# Wii_U_GamePad.net
KiCad netlist of a schematic drawn in EAGLE
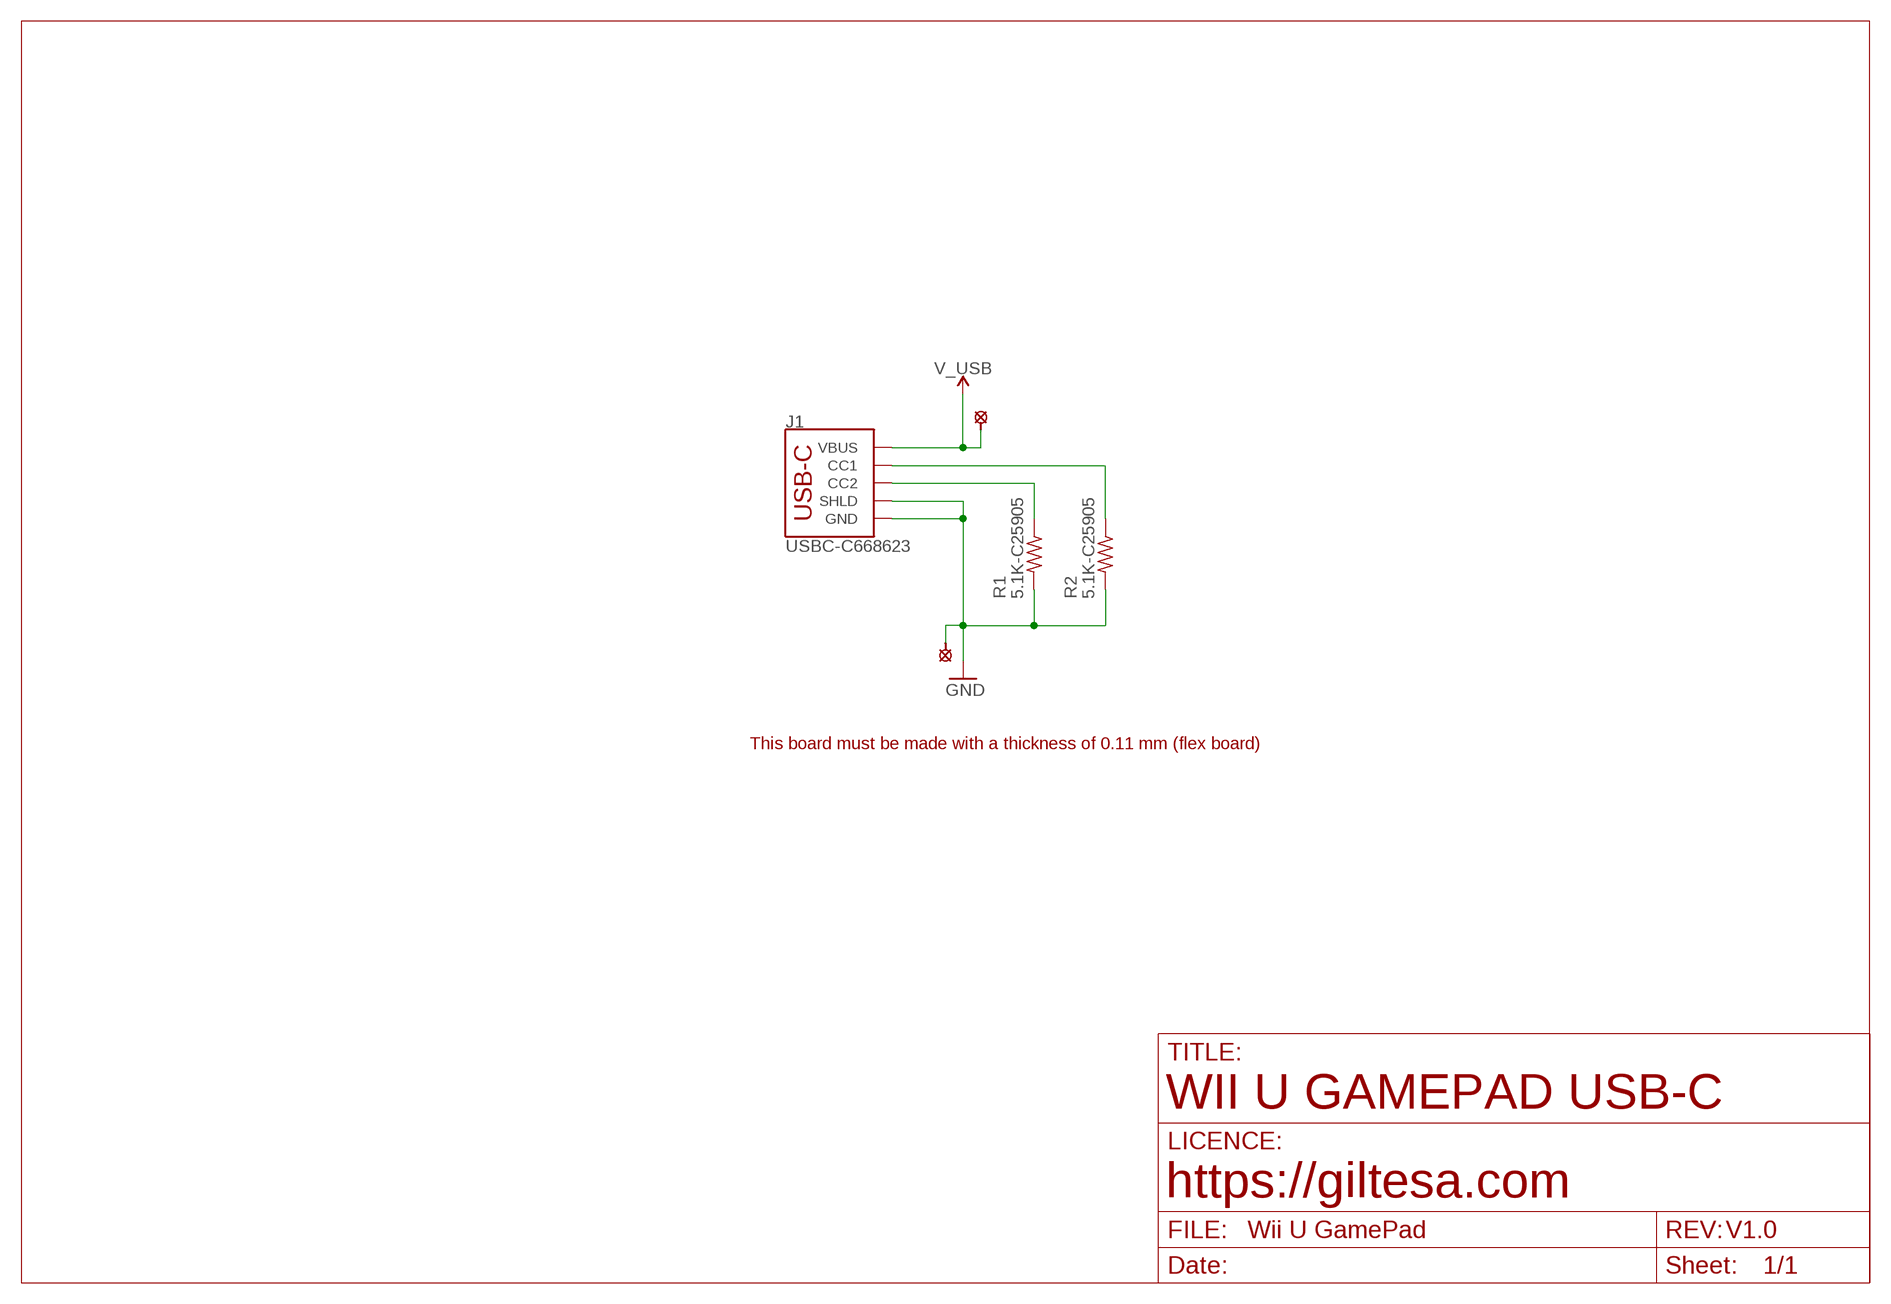
[diagram p0: schematic, sheet 1]

(export (version "E")
  (design (tool "Eeschema 10.0.6"))
  (components
    (comp (ref "J1")
      (value "USBC-C668623")
      (footprint "eagle-import:USB-C_6P_SMD_WIIU")
      (libsource (lib "eagle-import") (part "USB-C_6P_WIIU"))
    )
    (comp (ref "R1")
      (value "5.1K-C25905")
      (footprint "eagle-import:R0402")
      (libsource (lib "eagle-import") (part "R0402"))
    )
    (comp (ref "R2")
      (value "5.1K-C25905")
      (footprint "eagle-import:R0402")
      (libsource (lib "eagle-import") (part "R0402"))
    )
    (comp (ref "U$1")
      (value "PAD_1.7")
      (footprint "eagle-import:PAD_1.7")
      (libsource (lib "eagle-import") (part "PAD_1.7"))
    )
    (comp (ref "U$2")
      (value "PAD_1.7")
      (footprint "eagle-import:PAD_1.7")
      (libsource (lib "eagle-import") (part "PAD_1.7"))
    )
  )
  (nets
    (net (code "1") (name "GND") (class "Default")
      (node (ref "J1") (pin "A12-GND") (pinfunction "GND_A12-GND") (pintype "bidirectional"))
      (node (ref "J1") (pin "B12-GND") (pinfunction "GND_B12-GND") (pintype "bidirectional"))
      (node (ref "J1") (pin "SHLD") (pinfunction "SHLD_SHLD") (pintype "bidirectional"))
      (node (ref "R1") (pin "2") (pinfunction "2_2") (pintype "passive"))
      (node (ref "R2") (pin "2") (pinfunction "2_2") (pintype "passive"))
      (node (ref "U$2") (pin "P$1") (pinfunction "P$1_P$1") (pintype "bidirectional"))
    )
    (net (code "2") (name "Net-(J1-CC1)") (class "Default")
      (node (ref "J1") (pin "A5") (pinfunction "CC1_A5") (pintype "bidirectional"))
      (node (ref "R2") (pin "1") (pinfunction "1_1") (pintype "passive"))
    )
    (net (code "3") (name "Net-(J1-CC2)") (class "Default")
      (node (ref "J1") (pin "B5") (pinfunction "CC2_B5") (pintype "bidirectional"))
      (node (ref "R1") (pin "1") (pinfunction "1_1") (pintype "passive"))
    )
    (net (code "4") (name "V_USB") (class "Default")
      (node (ref "J1") (pin "A9-VBUS") (pinfunction "VBUS_A9-VBUS") (pintype "bidirectional"))
      (node (ref "J1") (pin "B9-VBUS") (pinfunction "VBUS_B9-VBUS") (pintype "bidirectional"))
      (node (ref "U$1") (pin "P$1") (pinfunction "P$1_P$1") (pintype "bidirectional"))
    )
  )
)
